# robo1.net
KiCad netlist of a schematic drawn in EAGLE
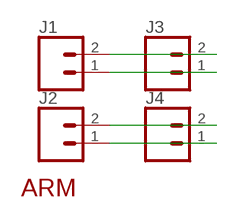
[diagram p0: schematic, sheet 1]

(export (version "E")
  (design (tool "Eeschema 10.0.6"))
  (components
    (comp (ref "J1")
      (value "CONN_02LOCK")
      (footprint "eagle-import:1X02_LOCK")
      (libsource (lib "eagle-import") (part "CONN_02LOCK"))
    )
    (comp (ref "J2")
      (value "CONN_02LOCK")
      (footprint "eagle-import:1X02_LOCK")
      (libsource (lib "eagle-import") (part "CONN_02LOCK"))
    )
    (comp (ref "J3")
      (value "CONN_02LOCK")
      (footprint "eagle-import:1X02_LOCK")
      (libsource (lib "eagle-import") (part "CONN_02LOCK"))
    )
    (comp (ref "J4")
      (value "CONN_02LOCK")
      (footprint "eagle-import:1X02_LOCK")
      (libsource (lib "eagle-import") (part "CONN_02LOCK"))
    )
    (comp (ref "U$1")
      (value "ARMROBO1")
      (footprint "eagle-import:ROBOT1")
      (libsource (lib "eagle-import") (part "ARMROBO1"))
    )
  )
  (nets
    (net (code "1") (name "Net-(J1-Pad1)") (class "Default")
      (node (ref "J1") (pin "1") (pinfunction "1_1") (pintype "passive"))
      (node (ref "J3") (pin "1") (pinfunction "1_1") (pintype "passive"))
    )
    (net (code "2") (name "Net-(J1-Pad2)") (class "Default")
      (node (ref "J1") (pin "2") (pinfunction "2_2") (pintype "passive"))
      (node (ref "J3") (pin "2") (pinfunction "2_2") (pintype "passive"))
    )
    (net (code "3") (name "Net-(J2-Pad1)") (class "Default")
      (node (ref "J2") (pin "1") (pinfunction "1_1") (pintype "passive"))
      (node (ref "J4") (pin "1") (pinfunction "1_1") (pintype "passive"))
    )
    (net (code "4") (name "Net-(J2-Pad2)") (class "Default")
      (node (ref "J2") (pin "2") (pinfunction "2_2") (pintype "passive"))
      (node (ref "J4") (pin "2") (pinfunction "2_2") (pintype "passive"))
    )
  )
)
